# SignalGen_DualChannel.net
KiCad netlist of a schematic drawn in Altium Designer
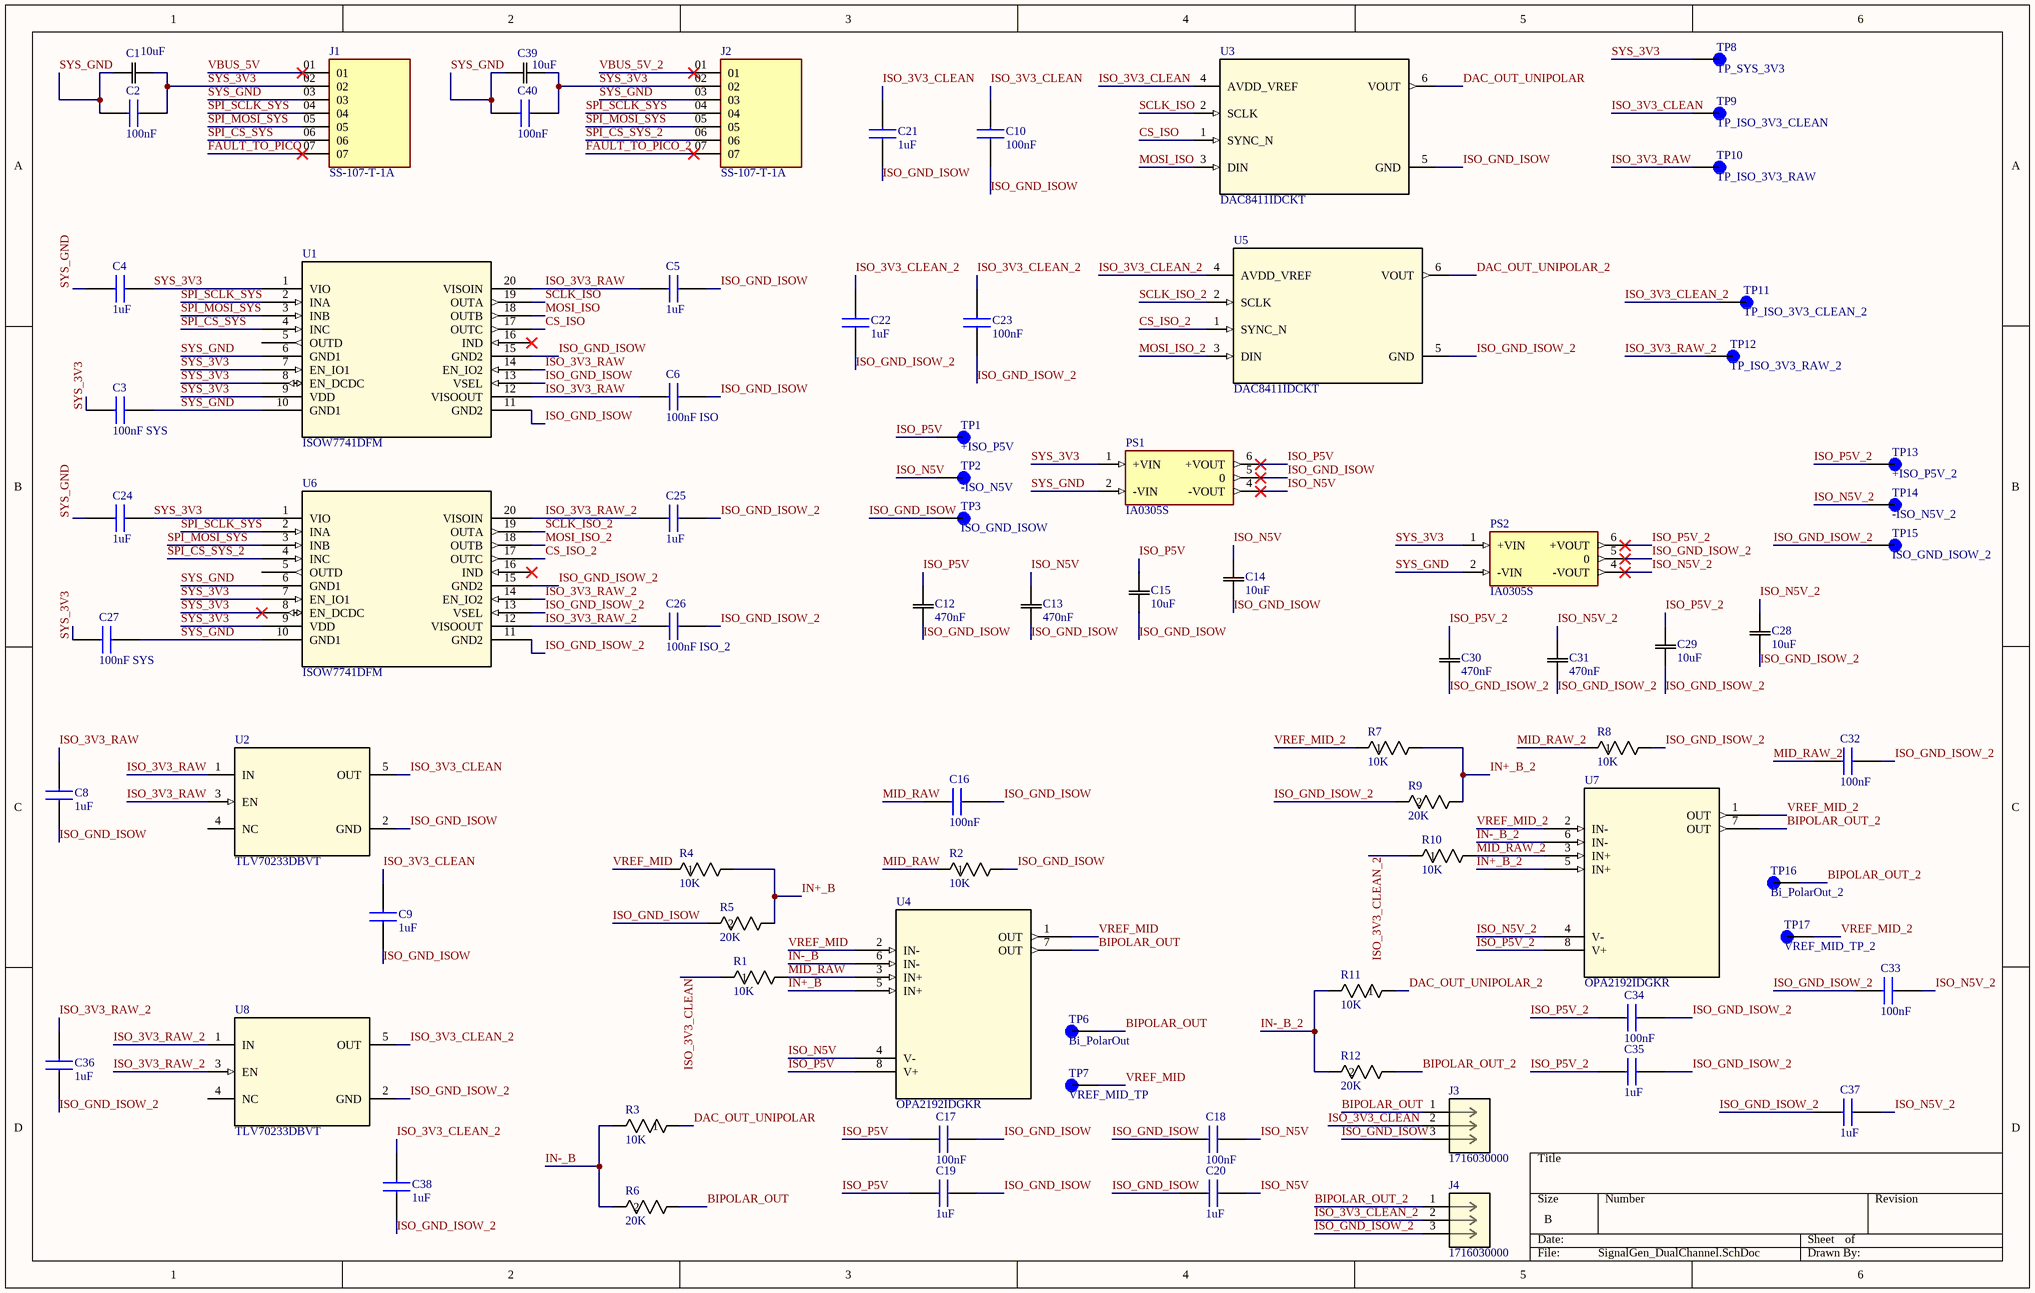
[diagram p0: SignalGen_DualChannel.SchDoc]

(export (version "E")
  (design (tool "Eeschema 10.0.6"))
  (components
    (comp (ref "C1")
      (value "10uF")
      (footprint "G-21_MUR")
      (description "Description")
      (fields
        (field (name "MANUFACTURER_PART_NUMBER") "GRM21BR61E106KA73L")
        (field (name "COPYRIGHT") "Copyright (C) 2025 Ultra Librarian. All rights reserved.")
      )
      (libsource (lib "GRM21BR61E106KA73L") (part "GRM21BR61E106KA73L"))
    )
    (comp (ref "C2")
      (value "100nF")
      (footprint "CAPC1608X90N")
      (description "Cap Ceramic 0.1uF 25V X7R 10% Pad SMD 0603 125C T/R")
      (fields
        (field (name "MOUSER PART NUMBER") "603-CC603KRX7R8BB104")
        (field (name "MANUFACTURER_PART_NUMBER") "CC0603KRX7R8BB104")
      )
      (libsource (lib "CC0603KRX7R8BB104") (part "CC0603KRX7R8BB104"))
    )
    (comp (ref "C3")
      (value "100nF SYS")
      (footprint "CAPC1608X90N")
      (description "Cap Ceramic 0.1uF 25V X7R 10% Pad SMD 0603 125C T/R")
      (fields
        (field (name "MOUSER PART NUMBER") "603-CC603KRX7R8BB104")
        (field (name "MANUFACTURER_PART_NUMBER") "CC0603KRX7R8BB104")
      )
      (libsource (lib "CC0603KRX7R8BB104") (part "CC0603KRX7R8BB104"))
    )
    (comp (ref "C4")
      (value "1uF")
      (footprint "INDC1608X90N")
      (description "Taiyo Yuden CAP, MLCC, 0603, 16V, X7R, 1 uF 10 %, T&R")
      (fields (field (name "MANUFACTURER_PART_NUMBER") "MBASE168SB7105KTNA18"))
      (libsource (lib "MBASE168SB7105KTNA18") (part "MBASE168SB7105KTNA18"))
    )
    (comp (ref "C5")
      (value "1uF")
      (footprint "INDC1608X90N")
      (description "Taiyo Yuden CAP, MLCC, 0603, 16V, X7R, 1 uF 10 %, T&R")
      (fields (field (name "MANUFACTURER_PART_NUMBER") "MBASE168SB7105KTNA18"))
      (libsource (lib "MBASE168SB7105KTNA18") (part "MBASE168SB7105KTNA18"))
    )
    (comp (ref "C6")
      (value "100nF ISO")
      (footprint "CAPC1608X90N")
      (description "Cap Ceramic 0.1uF 25V X7R 10% Pad SMD 0603 125C T/R")
      (fields
        (field (name "MOUSER PART NUMBER") "603-CC603KRX7R8BB104")
        (field (name "MANUFACTURER_PART_NUMBER") "CC0603KRX7R8BB104")
      )
      (libsource (lib "CC0603KRX7R8BB104") (part "CC0603KRX7R8BB104"))
    )
    (comp (ref "C8")
      (value "1uF")
      (footprint "INDC1608X90N")
      (description "Taiyo Yuden CAP, MLCC, 0603, 16V, X7R, 1 uF 10 %, T&R")
      (fields (field (name "MANUFACTURER_PART_NUMBER") "MBASE168SB7105KTNA18"))
      (libsource (lib "MBASE168SB7105KTNA18") (part "MBASE168SB7105KTNA18"))
    )
    (comp (ref "C9")
      (value "1uF")
      (footprint "INDC1608X90N")
      (description "Taiyo Yuden CAP, MLCC, 0603, 16V, X7R, 1 uF 10 %, T&R")
      (fields (field (name "MANUFACTURER_PART_NUMBER") "MBASE168SB7105KTNA18"))
      (libsource (lib "MBASE168SB7105KTNA18") (part "MBASE168SB7105KTNA18"))
    )
    (comp (ref "C10")
      (value "100nF")
      (footprint "CAPC1608X90N")
      (description "Cap Ceramic 0.1uF 25V X7R 10% Pad SMD 0603 125C T/R")
      (fields
        (field (name "MOUSER PART NUMBER") "603-CC603KRX7R8BB104")
        (field (name "MANUFACTURER_PART_NUMBER") "CC0603KRX7R8BB104")
      )
      (libsource (lib "CC0603KRX7R8BB104") (part "CC0603KRX7R8BB104"))
    )
    (comp (ref "C12")
      (value "470nF")
      (footprint "CAP_1608_TDK")
      (description "CAPACITOR; SMT (0603); CERAMIC CHIP; 0.47UF; 50V; TOL=10%; TG=-55 DEGC TO +125 DEGC; TC=X7R; AUTO")
      (fields
        (field (name "MANUFACTURER_PART_NUMBER") "C1608X7R1H474K080AC")
        (field (name "COPYRIGHT") "Copyright (C) 2026 Ultra Librarian. All rights reserved.")
      )
      (libsource (lib "C1608X7R1H474K080AC") (part "C1608X7R1H474K080AC"))
    )
    (comp (ref "C13")
      (value "470nF")
      (footprint "CAP_1608_TDK")
      (description "CAPACITOR; SMT (0603); CERAMIC CHIP; 0.47UF; 50V; TOL=10%; TG=-55 DEGC TO +125 DEGC; TC=X7R; AUTO")
      (fields
        (field (name "MANUFACTURER_PART_NUMBER") "C1608X7R1H474K080AC")
        (field (name "COPYRIGHT") "Copyright (C) 2026 Ultra Librarian. All rights reserved.")
      )
      (libsource (lib "C1608X7R1H474K080AC") (part "C1608X7R1H474K080AC"))
    )
    (comp (ref "C14")
      (value "10uF")
      (footprint "G-21_MUR")
      (description "Description")
      (fields
        (field (name "MANUFACTURER_PART_NUMBER") "GRM21BR61E106KA73L")
        (field (name "COPYRIGHT") "Copyright (C) 2025 Ultra Librarian. All rights reserved.")
      )
      (libsource (lib "GRM21BR61E106KA73L") (part "GRM21BR61E106KA73L"))
    )
    (comp (ref "C15")
      (value "10uF")
      (footprint "G-21_MUR")
      (description "Description")
      (fields
        (field (name "MANUFACTURER_PART_NUMBER") "GRM21BR61E106KA73L")
        (field (name "COPYRIGHT") "Copyright (C) 2025 Ultra Librarian. All rights reserved.")
      )
      (libsource (lib "GRM21BR61E106KA73L") (part "GRM21BR61E106KA73L"))
    )
    (comp (ref "C16")
      (value "100nF")
      (footprint "CAPC1608X90N")
      (description "Cap Ceramic 0.1uF 25V X7R 10% Pad SMD 0603 125C T/R")
      (fields
        (field (name "MOUSER PART NUMBER") "603-CC603KRX7R8BB104")
        (field (name "MANUFACTURER_PART_NUMBER") "CC0603KRX7R8BB104")
      )
      (libsource (lib "CC0603KRX7R8BB104") (part "CC0603KRX7R8BB104"))
    )
    (comp (ref "C17")
      (value "100nF")
      (footprint "CAPC1608X90N")
      (description "Cap Ceramic 0.1uF 25V X7R 10% Pad SMD 0603 125C T/R")
      (fields
        (field (name "MOUSER PART NUMBER") "603-CC603KRX7R8BB104")
        (field (name "MANUFACTURER_PART_NUMBER") "CC0603KRX7R8BB104")
      )
      (libsource (lib "CC0603KRX7R8BB104") (part "CC0603KRX7R8BB104"))
    )
    (comp (ref "C18")
      (value "100nF")
      (footprint "CAPC1608X90N")
      (description "Cap Ceramic 0.1uF 25V X7R 10% Pad SMD 0603 125C T/R")
      (fields
        (field (name "MOUSER PART NUMBER") "603-CC603KRX7R8BB104")
        (field (name "MANUFACTURER_PART_NUMBER") "CC0603KRX7R8BB104")
      )
      (libsource (lib "CC0603KRX7R8BB104") (part "CC0603KRX7R8BB104"))
    )
    (comp (ref "C19")
      (value "1uF")
      (footprint "INDC1608X90N")
      (description "Taiyo Yuden CAP, MLCC, 0603, 16V, X7R, 1 uF 10 %, T&R")
      (fields (field (name "MANUFACTURER_PART_NUMBER") "MBASE168SB7105KTNA18"))
      (libsource (lib "MBASE168SB7105KTNA18") (part "MBASE168SB7105KTNA18"))
    )
    (comp (ref "C20")
      (value "1uF")
      (footprint "INDC1608X90N")
      (description "Taiyo Yuden CAP, MLCC, 0603, 16V, X7R, 1 uF 10 %, T&R")
      (fields (field (name "MANUFACTURER_PART_NUMBER") "MBASE168SB7105KTNA18"))
      (libsource (lib "MBASE168SB7105KTNA18") (part "MBASE168SB7105KTNA18"))
    )
    (comp (ref "C21")
      (value "1uF")
      (footprint "INDC1608X90N")
      (description "Taiyo Yuden CAP, MLCC, 0603, 16V, X7R, 1 uF 10 %, T&R")
      (fields (field (name "MANUFACTURER_PART_NUMBER") "MBASE168SB7105KTNA18"))
      (libsource (lib "MBASE168SB7105KTNA18") (part "MBASE168SB7105KTNA18"))
    )
    (comp (ref "C22")
      (value "1uF")
      (footprint "INDC1608X90N")
      (description "Taiyo Yuden CAP, MLCC, 0603, 16V, X7R, 1 uF 10 %, T&R")
      (fields (field (name "MANUFACTURER_PART_NUMBER") "MBASE168SB7105KTNA18"))
      (libsource (lib "MBASE168SB7105KTNA18") (part "MBASE168SB7105KTNA18"))
    )
    (comp (ref "C23")
      (value "100nF")
      (footprint "CAPC1608X90N")
      (description "Cap Ceramic 0.1uF 25V X7R 10% Pad SMD 0603 125C T/R")
      (fields
        (field (name "MOUSER PART NUMBER") "603-CC603KRX7R8BB104")
        (field (name "MANUFACTURER_PART_NUMBER") "CC0603KRX7R8BB104")
      )
      (libsource (lib "CC0603KRX7R8BB104") (part "CC0603KRX7R8BB104"))
    )
    (comp (ref "C24")
      (value "1uF")
      (footprint "INDC1608X90N")
      (description "Taiyo Yuden CAP, MLCC, 0603, 16V, X7R, 1 uF 10 %, T&R")
      (fields (field (name "MANUFACTURER_PART_NUMBER") "MBASE168SB7105KTNA18"))
      (libsource (lib "MBASE168SB7105KTNA18") (part "MBASE168SB7105KTNA18"))
    )
    (comp (ref "C25")
      (value "1uF")
      (footprint "INDC1608X90N")
      (description "Taiyo Yuden CAP, MLCC, 0603, 16V, X7R, 1 uF 10 %, T&R")
      (fields (field (name "MANUFACTURER_PART_NUMBER") "MBASE168SB7105KTNA18"))
      (libsource (lib "MBASE168SB7105KTNA18") (part "MBASE168SB7105KTNA18"))
    )
    (comp (ref "C26")
      (value "100nF ISO_2")
      (footprint "CAPC1608X90N")
      (description "Cap Ceramic 0.1uF 25V X7R 10% Pad SMD 0603 125C T/R")
      (fields
        (field (name "MOUSER PART NUMBER") "603-CC603KRX7R8BB104")
        (field (name "MANUFACTURER_PART_NUMBER") "CC0603KRX7R8BB104")
      )
      (libsource (lib "CC0603KRX7R8BB104") (part "CC0603KRX7R8BB104"))
    )
    (comp (ref "C27")
      (value "100nF SYS")
      (footprint "CAPC1608X90N")
      (description "Cap Ceramic 0.1uF 25V X7R 10% Pad SMD 0603 125C T/R")
      (fields
        (field (name "MOUSER PART NUMBER") "603-CC603KRX7R8BB104")
        (field (name "MANUFACTURER_PART_NUMBER") "CC0603KRX7R8BB104")
      )
      (libsource (lib "CC0603KRX7R8BB104") (part "CC0603KRX7R8BB104"))
    )
    (comp (ref "C28")
      (value "10uF")
      (footprint "G-21_MUR")
      (description "Description")
      (fields
        (field (name "MANUFACTURER_PART_NUMBER") "GRM21BR61E106KA73L")
        (field (name "COPYRIGHT") "Copyright (C) 2025 Ultra Librarian. All rights reserved.")
      )
      (libsource (lib "GRM21BR61E106KA73L") (part "GRM21BR61E106KA73L"))
    )
    (comp (ref "C29")
      (value "10uF")
      (footprint "G-21_MUR")
      (description "Description")
      (fields
        (field (name "MANUFACTURER_PART_NUMBER") "GRM21BR61E106KA73L")
        (field (name "COPYRIGHT") "Copyright (C) 2025 Ultra Librarian. All rights reserved.")
      )
      (libsource (lib "GRM21BR61E106KA73L") (part "GRM21BR61E106KA73L"))
    )
    (comp (ref "C30")
      (value "470nF")
      (footprint "CAP_1608_TDK")
      (description "CAPACITOR; SMT (0603); CERAMIC CHIP; 0.47UF; 50V; TOL=10%; TG=-55 DEGC TO +125 DEGC; TC=X7R; AUTO")
      (fields
        (field (name "MANUFACTURER_PART_NUMBER") "C1608X7R1H474K080AC")
        (field (name "COPYRIGHT") "Copyright (C) 2026 Ultra Librarian. All rights reserved.")
      )
      (libsource (lib "C1608X7R1H474K080AC") (part "C1608X7R1H474K080AC"))
    )
    (comp (ref "C31")
      (value "470nF")
      (footprint "CAP_1608_TDK")
      (description "CAPACITOR; SMT (0603); CERAMIC CHIP; 0.47UF; 50V; TOL=10%; TG=-55 DEGC TO +125 DEGC; TC=X7R; AUTO")
      (fields
        (field (name "MANUFACTURER_PART_NUMBER") "C1608X7R1H474K080AC")
        (field (name "COPYRIGHT") "Copyright (C) 2026 Ultra Librarian. All rights reserved.")
      )
      (libsource (lib "C1608X7R1H474K080AC") (part "C1608X7R1H474K080AC"))
    )
    (comp (ref "C32")
      (value "100nF")
      (footprint "CAPC1608X90N")
      (description "Cap Ceramic 0.1uF 25V X7R 10% Pad SMD 0603 125C T/R")
      (fields
        (field (name "MOUSER PART NUMBER") "603-CC603KRX7R8BB104")
        (field (name "MANUFACTURER_PART_NUMBER") "CC0603KRX7R8BB104")
      )
      (libsource (lib "CC0603KRX7R8BB104") (part "CC0603KRX7R8BB104"))
    )
    (comp (ref "C33")
      (value "100nF")
      (footprint "CAPC1608X90N")
      (description "Cap Ceramic 0.1uF 25V X7R 10% Pad SMD 0603 125C T/R")
      (fields
        (field (name "MOUSER PART NUMBER") "603-CC603KRX7R8BB104")
        (field (name "MANUFACTURER_PART_NUMBER") "CC0603KRX7R8BB104")
      )
      (libsource (lib "CC0603KRX7R8BB104") (part "CC0603KRX7R8BB104"))
    )
    (comp (ref "C34")
      (value "100nF")
      (footprint "CAPC1608X90N")
      (description "Cap Ceramic 0.1uF 25V X7R 10% Pad SMD 0603 125C T/R")
      (fields
        (field (name "MOUSER PART NUMBER") "603-CC603KRX7R8BB104")
        (field (name "MANUFACTURER_PART_NUMBER") "CC0603KRX7R8BB104")
      )
      (libsource (lib "CC0603KRX7R8BB104") (part "CC0603KRX7R8BB104"))
    )
    (comp (ref "C35")
      (value "1uF")
      (footprint "INDC1608X90N")
      (description "Taiyo Yuden CAP, MLCC, 0603, 16V, X7R, 1 uF 10 %, T&R")
      (fields (field (name "MANUFACTURER_PART_NUMBER") "MBASE168SB7105KTNA18"))
      (libsource (lib "MBASE168SB7105KTNA18") (part "MBASE168SB7105KTNA18"))
    )
    (comp (ref "C36")
      (value "1uF")
      (footprint "INDC1608X90N")
      (description "Taiyo Yuden CAP, MLCC, 0603, 16V, X7R, 1 uF 10 %, T&R")
      (fields (field (name "MANUFACTURER_PART_NUMBER") "MBASE168SB7105KTNA18"))
      (libsource (lib "MBASE168SB7105KTNA18") (part "MBASE168SB7105KTNA18"))
    )
    (comp (ref "C37")
      (value "1uF")
      (footprint "INDC1608X90N")
      (description "Taiyo Yuden CAP, MLCC, 0603, 16V, X7R, 1 uF 10 %, T&R")
      (fields (field (name "MANUFACTURER_PART_NUMBER") "MBASE168SB7105KTNA18"))
      (libsource (lib "MBASE168SB7105KTNA18") (part "MBASE168SB7105KTNA18"))
    )
    (comp (ref "C38")
      (value "1uF")
      (footprint "INDC1608X90N")
      (description "Taiyo Yuden CAP, MLCC, 0603, 16V, X7R, 1 uF 10 %, T&R")
      (fields (field (name "MANUFACTURER_PART_NUMBER") "MBASE168SB7105KTNA18"))
      (libsource (lib "MBASE168SB7105KTNA18") (part "MBASE168SB7105KTNA18"))
    )
    (comp (ref "C39")
      (value "10uF")
      (footprint "G-21_MUR")
      (description "Description")
      (fields
        (field (name "MANUFACTURER_PART_NUMBER") "GRM21BR61E106KA73L")
        (field (name "COPYRIGHT") "Copyright (C) 2025 Ultra Librarian. All rights reserved.")
      )
      (libsource (lib "GRM21BR61E106KA73L") (part "GRM21BR61E106KA73L"))
    )
    (comp (ref "C40")
      (value "100nF")
      (footprint "CAPC1608X90N")
      (description "Cap Ceramic 0.1uF 25V X7R 10% Pad SMD 0603 125C T/R")
      (fields
        (field (name "MOUSER PART NUMBER") "603-CC603KRX7R8BB104")
        (field (name "MANUFACTURER_PART_NUMBER") "CC0603KRX7R8BB104")
      )
      (libsource (lib "CC0603KRX7R8BB104") (part "CC0603KRX7R8BB104"))
    )
    (comp (ref "J1")
      (value "SS-107-T-1A")
      (footprint "SAMTEC_SS-107-T-1A")
      (libsource (lib "SS-107-T-1A") (part "SS-107-T-1A"))
    )
    (comp (ref "J2")
      (value "SS-107-T-1A")
      (footprint "SAMTEC_SS-107-T-1A")
      (libsource (lib "SS-107-T-1A") (part "SS-107-T-1A"))
    )
    (comp (ref "J3")
      (value "1716030000")
      (footprint "CONN_LM 5.080390_WED")
      (description "Description")
      (fields (field (name "COPYRIGHT") "Copyright (C) 2025 Ultra Librarian. All rights reserved."))
      (libsource (lib "1716030000") (part "1716030000"))
    )
    (comp (ref "J4")
      (value "1716030000")
      (footprint "CONN_LM 5.080390_WED")
      (description "Description")
      (fields (field (name "COPYRIGHT") "Copyright (C) 2025 Ultra Librarian. All rights reserved."))
      (libsource (lib "1716030000") (part "1716030000"))
    )
    (comp (ref "PS1")
      (value "IA0305S")
      (footprint "XP_IA0305S")
      (description "DC DC CONVERTER +/-5V 1W")
      (libsource (lib "IA0305S") (part "IA0305S"))
    )
    (comp (ref "PS2")
      (value "IA0305S")
      (footprint "XP_IA0305S")
      (description "DC DC CONVERTER +/-5V 1W")
      (libsource (lib "IA0305S") (part "IA0305S"))
    )
    (comp (ref "R1")
      (value "10K")
      (footprint "RC0603N_YAG")
      (description "RES SMD 10kO 1% 1/10W 0603")
      (fields
        (field (name "MANUFACTURER_PART_NUMBER") "RC0603FR-0710KL")
        (field (name "COPYRIGHT") "Copyright (C) 2025 Ultra Librarian. All rights reserved.")
      )
      (libsource (lib "RC0603FR-0710KL") (part "RC0603FR-0710KL"))
    )
    (comp (ref "R2")
      (value "10K")
      (footprint "RC0603N_YAG")
      (description "RES SMD 10kO 1% 1/10W 0603")
      (fields
        (field (name "MANUFACTURER_PART_NUMBER") "RC0603FR-0710KL")
        (field (name "COPYRIGHT") "Copyright (C) 2025 Ultra Librarian. All rights reserved.")
      )
      (libsource (lib "RC0603FR-0710KL") (part "RC0603FR-0710KL"))
    )
    (comp (ref "R3")
      (value "10K")
      (footprint "RC0603N_YAG")
      (description "RES SMD 10kO 1% 1/10W 0603")
      (fields
        (field (name "MANUFACTURER_PART_NUMBER") "RC0603FR-0710KL")
        (field (name "COPYRIGHT") "Copyright (C) 2025 Ultra Librarian. All rights reserved.")
      )
      (libsource (lib "RC0603FR-0710KL") (part "RC0603FR-0710KL"))
    )
    (comp (ref "R4")
      (value "10K")
      (footprint "RC0603N_YAG")
      (description "RES SMD 10kO 1% 1/10W 0603")
      (fields
        (field (name "MANUFACTURER_PART_NUMBER") "RC0603FR-0710KL")
        (field (name "COPYRIGHT") "Copyright (C) 2025 Ultra Librarian. All rights reserved.")
      )
      (libsource (lib "RC0603FR-0710KL") (part "RC0603FR-0710KL"))
    )
    (comp (ref "R5")
      (value "20K")
      (footprint "RC0603N_YAG")
      (description "Description")
      (fields
        (field (name "MANUFACTURER_PART_NUMBER") "RC0603FR-0720KL")
        (field (name "COPYRIGHT") "Copyright (C) 2025 Ultra Librarian. All rights reserved.")
      )
      (libsource (lib "RC0603FR-0720KL") (part "RC0603FR-0720KL"))
    )
    (comp (ref "R6")
      (value "20K")
      (footprint "RC0603N_YAG")
      (description "Description")
      (fields
        (field (name "MANUFACTURER_PART_NUMBER") "RC0603FR-0720KL")
        (field (name "COPYRIGHT") "Copyright (C) 2025 Ultra Librarian. All rights reserved.")
      )
      (libsource (lib "RC0603FR-0720KL") (part "RC0603FR-0720KL"))
    )
    (comp (ref "R7")
      (value "10K")
      (footprint "RC0603N_YAG")
      (description "RES SMD 10kO 1% 1/10W 0603")
      (fields
        (field (name "MANUFACTURER_PART_NUMBER") "RC0603FR-0710KL")
        (field (name "COPYRIGHT") "Copyright (C) 2025 Ultra Librarian. All rights reserved.")
      )
      (libsource (lib "RC0603FR-0710KL") (part "RC0603FR-0710KL"))
    )
    (comp (ref "R8")
      (value "10K")
      (footprint "RC0603N_YAG")
      (description "RES SMD 10kO 1% 1/10W 0603")
      (fields
        (field (name "MANUFACTURER_PART_NUMBER") "RC0603FR-0710KL")
        (field (name "COPYRIGHT") "Copyright (C) 2025 Ultra Librarian. All rights reserved.")
      )
      (libsource (lib "RC0603FR-0710KL") (part "RC0603FR-0710KL"))
    )
    (comp (ref "R9")
      (value "20K")
      (footprint "RC0603N_YAG")
      (description "Description")
      (fields
        (field (name "MANUFACTURER_PART_NUMBER") "RC0603FR-0720KL")
        (field (name "COPYRIGHT") "Copyright (C) 2025 Ultra Librarian. All rights reserved.")
      )
      (libsource (lib "RC0603FR-0720KL") (part "RC0603FR-0720KL"))
    )
    (comp (ref "R10")
      (value "10K")
      (footprint "RC0603N_YAG")
      (description "RES SMD 10kO 1% 1/10W 0603")
      (fields
        (field (name "MANUFACTURER_PART_NUMBER") "RC0603FR-0710KL")
        (field (name "COPYRIGHT") "Copyright (C) 2025 Ultra Librarian. All rights reserved.")
      )
      (libsource (lib "RC0603FR-0710KL") (part "RC0603FR-0710KL"))
    )
    (comp (ref "R11")
      (value "10K")
      (footprint "RC0603N_YAG")
      (description "RES SMD 10kO 1% 1/10W 0603")
      (fields
        (field (name "MANUFACTURER_PART_NUMBER") "RC0603FR-0710KL")
        (field (name "COPYRIGHT") "Copyright (C) 2025 Ultra Librarian. All rights reserved.")
      )
      (libsource (lib "RC0603FR-0710KL") (part "RC0603FR-0710KL"))
    )
    (comp (ref "R12")
      (value "20K")
      (footprint "RC0603N_YAG")
      (description "Description")
      (fields
        (field (name "MANUFACTURER_PART_NUMBER") "RC0603FR-0720KL")
        (field (name "COPYRIGHT") "Copyright (C) 2025 Ultra Librarian. All rights reserved.")
      )
      (libsource (lib "RC0603FR-0720KL") (part "RC0603FR-0720KL"))
    )
    (comp (ref "TP1")
      (value "+ISO_P5V")
      (footprint "KEYSTONE_5016")
      (description "Test Point Compact SMT Phos Bronze/Silver 1000pc Tape & Reel ¦ Keystone Electronics 5016")
      (fields (field (name "MF") "Keystone Electronics") (field (name "MP") "5016"))
      (libsource (lib "5016") (part "5016"))
    )
    (comp (ref "TP2")
      (value "-ISO_N5V")
      (footprint "KEYSTONE_5016")
      (description "Test Point Compact SMT Phos Bronze/Silver 1000pc Tape & Reel ¦ Keystone Electronics 5016")
      (fields (field (name "MF") "Keystone Electronics") (field (name "MP") "5016"))
      (libsource (lib "5016") (part "5016"))
    )
    (comp (ref "TP3")
      (value "ISO_GND_ISOW")
      (footprint "KEYSTONE_5016")
      (description "Test Point Compact SMT Phos Bronze/Silver 1000pc Tape & Reel ¦ Keystone Electronics 5016")
      (fields (field (name "MF") "Keystone Electronics") (field (name "MP") "5016"))
      (libsource (lib "5016") (part "5016"))
    )
    (comp (ref "TP6")
      (value "Bi_PolarOut")
      (footprint "KEYSTONE_5016")
      (description "Test Point Compact SMT Phos Bronze/Silver 1000pc Tape & Reel ¦ Keystone Electronics 5016")
      (fields (field (name "MF") "Keystone Electronics") (field (name "MP") "5016"))
      (libsource (lib "5016") (part "5016"))
    )
    (comp (ref "TP7")
      (value "VREF_MID_TP")
      (footprint "KEYSTONE_5016")
      (description "Test Point Compact SMT Phos Bronze/Silver 1000pc Tape & Reel ¦ Keystone Electronics 5016")
      (fields (field (name "MF") "Keystone Electronics") (field (name "MP") "5016"))
      (libsource (lib "5016") (part "5016"))
    )
    (comp (ref "TP8")
      (value "TP_SYS_3V3")
      (footprint "KEYSTONE_5016")
      (description "Test Point Compact SMT Phos Bronze/Silver 1000pc Tape & Reel ¦ Keystone Electronics 5016")
      (fields (field (name "MF") "Keystone Electronics") (field (name "MP") "5016"))
      (libsource (lib "5016") (part "5016"))
    )
    (comp (ref "TP9")
      (value "TP_ISO_3V3_CLEAN")
      (footprint "KEYSTONE_5016")
      (description "Test Point Compact SMT Phos Bronze/Silver 1000pc Tape & Reel ¦ Keystone Electronics 5016")
      (fields (field (name "MF") "Keystone Electronics") (field (name "MP") "5016"))
      (libsource (lib "5016") (part "5016"))
    )
    (comp (ref "TP10")
      (value "TP_ISO_3V3_RAW")
      (footprint "KEYSTONE_5016")
      (description "Test Point Compact SMT Phos Bronze/Silver 1000pc Tape & Reel ¦ Keystone Electronics 5016")
      (fields (field (name "MF") "Keystone Electronics") (field (name "MP") "5016"))
      (libsource (lib "5016") (part "5016"))
    )
    (comp (ref "TP11")
      (value "TP_ISO_3V3_CLEAN_2")
      (footprint "KEYSTONE_5016")
      (description "Test Point Compact SMT Phos Bronze/Silver 1000pc Tape & Reel ¦ Keystone Electronics 5016")
      (fields (field (name "MF") "Keystone Electronics") (field (name "MP") "5016"))
      (libsource (lib "5016") (part "5016"))
    )
    (comp (ref "TP12")
      (value "TP_ISO_3V3_RAW_2")
      (footprint "KEYSTONE_5016")
      (description "Test Point Compact SMT Phos Bronze/Silver 1000pc Tape & Reel ¦ Keystone Electronics 5016")
      (fields (field (name "MF") "Keystone Electronics") (field (name "MP") "5016"))
      (libsource (lib "5016") (part "5016"))
    )
    (comp (ref "TP13")
      (value "+ISO_P5V_2")
      (footprint "KEYSTONE_5016")
      (description "Test Point Compact SMT Phos Bronze/Silver 1000pc Tape & Reel ¦ Keystone Electronics 5016")
      (fields (field (name "MF") "Keystone Electronics") (field (name "MP") "5016"))
      (libsource (lib "5016") (part "5016"))
    )
    (comp (ref "TP14")
      (value "-ISO_N5V_2")
      (footprint "KEYSTONE_5016")
      (description "Test Point Compact SMT Phos Bronze/Silver 1000pc Tape & Reel ¦ Keystone Electronics 5016")
      (fields (field (name "MF") "Keystone Electronics") (field (name "MP") "5016"))
      (libsource (lib "5016") (part "5016"))
    )
    (comp (ref "TP15")
      (value "ISO_GND_ISOW_2")
      (footprint "KEYSTONE_5016")
      (description "Test Point Compact SMT Phos Bronze/Silver 1000pc Tape & Reel ¦ Keystone Electronics 5016")
      (fields (field (name "MF") "Keystone Electronics") (field (name "MP") "5016"))
      (libsource (lib "5016") (part "5016"))
    )
    (comp (ref "TP16")
      (value "Bi_PolarOut_2")
      (footprint "KEYSTONE_5016")
      (description "Test Point Compact SMT Phos Bronze/Silver 1000pc Tape & Reel ¦ Keystone Electronics 5016")
      (fields (field (name "MF") "Keystone Electronics") (field (name "MP") "5016"))
      (libsource (lib "5016") (part "5016"))
    )
    (comp (ref "TP17")
      (value "VREF_MID_TP_2")
      (footprint "KEYSTONE_5016")
      (description "Test Point Compact SMT Phos Bronze/Silver 1000pc Tape & Reel ¦ Keystone Electronics 5016")
      (fields (field (name "MF") "Keystone Electronics") (field (name "MP") "5016"))
      (libsource (lib "5016") (part "5016"))
    )
    (comp (ref "U1")
      (value "ISOW7741DFM")
      (footprint "SOIC20_DFM_TEX")
      (fields (field (name "COPYRIGHT") "Copyright (C) 2026 Ultra Librarian. All rights reserved."))
      (libsource (lib "ISOW7741DFM") (part "ISOW7741DFM"))
    )
    (comp (ref "U2")
      (value "TLV70233DBVT")
      (footprint "DBV0005A_N")
      (description "300-mA, high-PSRR, low-IQ, low-dropout voltage regulator with enable 5-SOT-23 -40 to 125")
      (fields
        (field (name "PARTNUMBER") "TLV70212DBVR")
        (field (name "ALTERNATE_PARTNUMBER") "TLV70212DBVT")
        (field (name "COPYRIGHT") "Copyright (C) 2026 Ultra Librarian. All rights reserved.")
      )
      (libsource (lib "TLV70233DBVT") (part "TLV70233DBVT"))
    )
    (comp (ref "U3")
      (value "DAC8411IDCKT")
      (footprint "DCK0006A_N")
      (description "16bit, Single Channel, 80uA, 2.0V-5.5V DAC in SC70 Package 6-SC70 -40 to 125")
      (fields
        (field (name "PARTNUMBER") "DAC8411IDCKR")
        (field (name "MANUFACTURER") "Texas Instruments")
        (field (name "COPYRIGHT") "Copyright (C) 2025 Ultra Librarian. All rights reserved.")
      )
      (libsource (lib "DAC8411IDCKT") (part "DAC8411IDCKT"))
    )
    (comp (ref "U4")
      (value "OPA2192IDGKR")
      (footprint "DGK0008A_N_TEX")
      (fields (field (name "COPYRIGHT") "Copyright (C) 2025 Ultra Librarian. All rights reserved."))
      (libsource (lib "OPA2192IDGKR") (part "OPA2192IDGKR"))
    )
    (comp (ref "U5")
      (value "DAC8411IDCKT")
      (footprint "DCK0006A_N")
      (description "16bit, Single Channel, 80uA, 2.0V-5.5V DAC in SC70 Package 6-SC70 -40 to 125")
      (fields
        (field (name "PARTNUMBER") "DAC8411IDCKR")
        (field (name "MANUFACTURER") "Texas Instruments")
        (field (name "COPYRIGHT") "Copyright (C) 2025 Ultra Librarian. All rights reserved.")
      )
      (libsource (lib "DAC8411IDCKT") (part "DAC8411IDCKT"))
    )
    (comp (ref "U6")
      (value "ISOW7741DFM")
      (footprint "SOIC20_DFM_TEX")
      (fields (field (name "COPYRIGHT") "Copyright (C) 2026 Ultra Librarian. All rights reserved."))
      (libsource (lib "ISOW7741DFM") (part "ISOW7741DFM"))
    )
    (comp (ref "U7")
      (value "OPA2192IDGKR")
      (footprint "DGK0008A_N_TEX")
      (fields (field (name "COPYRIGHT") "Copyright (C) 2025 Ultra Librarian. All rights reserved."))
      (libsource (lib "OPA2192IDGKR") (part "OPA2192IDGKR"))
    )
    (comp (ref "U8")
      (value "TLV70233DBVT")
      (footprint "DBV0005A_N")
      (description "300-mA, high-PSRR, low-IQ, low-dropout voltage regulator with enable 5-SOT-23 -40 to 125")
      (fields
        (field (name "PARTNUMBER") "TLV70212DBVR")
        (field (name "ALTERNATE_PARTNUMBER") "TLV70212DBVT")
        (field (name "COPYRIGHT") "Copyright (C) 2026 Ultra Librarian. All rights reserved.")
      )
      (libsource (lib "TLV70233DBVT") (part "TLV70233DBVT"))
    )
  )
  (nets
    (net (code "1") (name "/BIPOLAR_OUT") (class "Default")
      (node (ref "J3") (pin "1") (pinfunction "1_1") (pintype "passive"))
      (node (ref "R6") (pin "1") (pinfunction "1_1") (pintype "passive"))
      (node (ref "TP6") (pin "TP") (pinfunction "TP_TP") (pintype "passive"))
      (node (ref "U4") (pin "7") (pinfunction "OUT_7") (pintype "output"))
    )
    (net (code "2") (name "/BIPOLAR_OUT_2") (class "Default")
      (node (ref "J4") (pin "1") (pinfunction "1_1") (pintype "passive"))
      (node (ref "R12") (pin "1") (pinfunction "1_1") (pintype "passive"))
      (node (ref "TP16") (pin "TP") (pinfunction "TP_TP") (pintype "passive"))
      (node (ref "U7") (pin "7") (pinfunction "OUT_7") (pintype "output"))
    )
    (net (code "3") (name "/CS_ISO") (class "Default")
      (node (ref "U1") (pin "17") (pinfunction "OUTC_17") (pintype "output"))
      (node (ref "U3") (pin "1") (pinfunction "SYNC_N_1") (pintype "input"))
    )
    (net (code "4") (name "/CS_ISO_2") (class "Default")
      (node (ref "U5") (pin "1") (pinfunction "SYNC_N_1") (pintype "input"))
      (node (ref "U6") (pin "17") (pinfunction "OUTC_17") (pintype "output"))
    )
    (net (code "5") (name "/DAC_OUT_UNIPOLAR") (class "Default")
      (node (ref "R3") (pin "1") (pinfunction "1_1") (pintype "passive"))
      (node (ref "U3") (pin "6") (pinfunction "VOUT_6") (pintype "output"))
    )
    (net (code "6") (name "/DAC_OUT_UNIPOLAR_2") (class "Default")
      (node (ref "R11") (pin "1") (pinfunction "1_1") (pintype "passive"))
      (node (ref "U5") (pin "6") (pinfunction "VOUT_6") (pintype "output"))
    )
    (net (code "7") (name "/FAULT_TO_PICO") (class "Default")
      (node (ref "J1") (pin "07") (pinfunction "07_07") (pintype "passive+no_connect"))
    )
    (net (code "8") (name "/FAULT_TO_PICO_2") (class "Default")
      (node (ref "J2") (pin "07") (pinfunction "07_07") (pintype "passive+no_connect"))
    )
    (net (code "9") (name "/IN+_B") (class "Default")
      (node (ref "R4") (pin "2") (pinfunction "2_2") (pintype "passive"))
      (node (ref "R5") (pin "1") (pinfunction "1_1") (pintype "passive"))
      (node (ref "U4") (pin "5") (pinfunction "IN+_5") (pintype "input"))
    )
    (net (code "10") (name "/IN+_B_2") (class "Default")
      (node (ref "R7") (pin "2") (pinfunction "2_2") (pintype "passive"))
      (node (ref "R9") (pin "1") (pinfunction "1_1") (pintype "passive"))
      (node (ref "U7") (pin "5") (pinfunction "IN+_5") (pintype "input"))
    )
    (net (code "11") (name "/IN-_B") (class "Default")
      (node (ref "R3") (pin "2") (pinfunction "2_2") (pintype "passive"))
      (node (ref "R6") (pin "2") (pinfunction "2_2") (pintype "passive"))
      (node (ref "U4") (pin "6") (pinfunction "IN-_6") (pintype "input"))
    )
    (net (code "12") (name "/IN-_B_2") (class "Default")
      (node (ref "R11") (pin "2") (pinfunction "2_2") (pintype "passive"))
      (node (ref "R12") (pin "2") (pinfunction "2_2") (pintype "passive"))
      (node (ref "U7") (pin "6") (pinfunction "IN-_6") (pintype "input"))
    )
    (net (code "13") (name "/ISO_3V3_CLEAN") (class "Default")
      (node (ref "C10") (pin "2") (pinfunction "2_2") (pintype "passive"))
      (node (ref "C21") (pin "2") (pinfunction "2_2") (pintype "passive"))
      (node (ref "C9") (pin "2") (pinfunction "2_2") (pintype "passive"))
      (node (ref "J3") (pin "2") (pinfunction "2_2") (pintype "passive"))
      (node (ref "R1") (pin "1") (pinfunction "1_1") (pintype "passive"))
      (node (ref "TP9") (pin "TP") (pinfunction "TP_TP") (pintype "passive"))
      (node (ref "U2") (pin "5") (pinfunction "OUT_5") (pintype "power_in"))
      (node (ref "U3") (pin "4") (pinfunction "AVDD_VREF_4") (pintype "power_in"))
    )
    (net (code "14") (name "/ISO_3V3_CLEAN_2") (class "Default")
      (node (ref "C22") (pin "2") (pinfunction "2_2") (pintype "passive"))
      (node (ref "C23") (pin "2") (pinfunction "2_2") (pintype "passive"))
      (node (ref "C38") (pin "2") (pinfunction "2_2") (pintype "passive"))
      (node (ref "J4") (pin "2") (pinfunction "2_2") (pintype "passive"))
      (node (ref "R10") (pin "1") (pinfunction "1_1") (pintype "passive"))
      (node (ref "TP11") (pin "TP") (pinfunction "TP_TP") (pintype "passive"))
      (node (ref "U5") (pin "4") (pinfunction "AVDD_VREF_4") (pintype "power_in"))
      (node (ref "U8") (pin "5") (pinfunction "OUT_5") (pintype "power_in"))
    )
    (net (code "15") (name "/ISO_3V3_RAW") (class "Default")
      (node (ref "C5") (pin "1") (pinfunction "1_1") (pintype "passive"))
      (node (ref "C6") (pin "2") (pinfunction "2_2") (pintype "passive"))
      (node (ref "C8") (pin "2") (pinfunction "2_2") (pintype "passive"))
      (node (ref "TP10") (pin "TP") (pinfunction "TP_TP") (pintype "passive"))
      (node (ref "U1") (pin "12") (pinfunction "VISOOUT_12") (pintype "power_in"))
      (node (ref "U1") (pin "14") (pinfunction "EN_IO2_14") (pintype "input"))
      (node (ref "U1") (pin "20") (pinfunction "VISOIN_20") (pintype "power_in"))
      (node (ref "U2") (pin "1") (pinfunction "IN_1") (pintype "power_in"))
      (node (ref "U2") (pin "3") (pinfunction "EN_3") (pintype "input"))
    )
    (net (code "16") (name "/ISO_3V3_RAW_2") (class "Default")
      (node (ref "C25") (pin "1") (pinfunction "1_1") (pintype "passive"))
      (node (ref "C26") (pin "2") (pinfunction "2_2") (pintype "passive"))
      (node (ref "C36") (pin "2") (pinfunction "2_2") (pintype "passive"))
      (node (ref "TP12") (pin "TP") (pinfunction "TP_TP") (pintype "passive"))
      (node (ref "U6") (pin "12") (pinfunction "VISOOUT_12") (pintype "power_in"))
      (node (ref "U6") (pin "14") (pinfunction "EN_IO2_14") (pintype "input"))
      (node (ref "U6") (pin "20") (pinfunction "VISOIN_20") (pintype "power_in"))
      (node (ref "U8") (pin "1") (pinfunction "IN_1") (pintype "power_in"))
      (node (ref "U8") (pin "3") (pinfunction "EN_3") (pintype "input"))
    )
    (net (code "17") (name "/ISO_GND_ISOW") (class "Default")
      (node (ref "C10") (pin "1") (pinfunction "1_1") (pintype "passive"))
      (node (ref "C12") (pin "1") (pinfunction "1_1") (pintype "passive"))
      (node (ref "C13") (pin "1") (pinfunction "1_1") (pintype "passive"))
      (node (ref "C14") (pin "1") (pinfunction "1_1") (pintype "passive"))
      (node (ref "C15") (pin "1") (pinfunction "1_1") (pintype "passive"))
      (node (ref "C16") (pin "2") (pinfunction "2_2") (pintype "passive"))
      (node (ref "C17") (pin "2") (pinfunction "2_2") (pintype "passive"))
      (node (ref "C18") (pin "1") (pinfunction "1_1") (pintype "passive"))
      (node (ref "C19") (pin "2") (pinfunction "2_2") (pintype "passive"))
      (node (ref "C20") (pin "1") (pinfunction "1_1") (pintype "passive"))
      (node (ref "C21") (pin "1") (pinfunction "1_1") (pintype "passive"))
      (node (ref "C5") (pin "2") (pinfunction "2_2") (pintype "passive"))
      (node (ref "C6") (pin "1") (pinfunction "1_1") (pintype "passive"))
      (node (ref "C8") (pin "1") (pinfunction "1_1") (pintype "passive"))
      (node (ref "C9") (pin "1") (pinfunction "1_1") (pintype "passive"))
      (node (ref "J3") (pin "3") (pinfunction "3_3") (pintype "passive"))
      (node (ref "PS1") (pin "5") (pinfunction "0_5") (pintype "output"))
      (node (ref "R2") (pin "2") (pinfunction "2_2") (pintype "passive"))
      (node (ref "R5") (pin "2") (pinfunction "2_2") (pintype "passive"))
      (node (ref "TP3") (pin "TP") (pinfunction "TP_TP") (pintype "passive"))
      (node (ref "U1") (pin "11") (pinfunction "GND2_11") (pintype "power_in"))
      (node (ref "U1") (pin "13") (pinfunction "VSEL_13") (pintype "input"))
      (node (ref "U1") (pin "15") (pinfunction "GND2_15") (pintype "power_in"))
      (node (ref "U2") (pin "2") (pinfunction "GND_2") (pintype "power_in"))
      (node (ref "U3") (pin "5") (pinfunction "GND_5") (pintype "power_in"))
    )
    (net (code "18") (name "/ISO_GND_ISOW_2") (class "Default")
      (node (ref "C22") (pin "1") (pinfunction "1_1") (pintype "passive"))
      (node (ref "C23") (pin "1") (pinfunction "1_1") (pintype "passive"))
      (node (ref "C25") (pin "2") (pinfunction "2_2") (pintype "passive"))
      (node (ref "C26") (pin "1") (pinfunction "1_1") (pintype "passive"))
      (node (ref "C28") (pin "1") (pinfunction "1_1") (pintype "passive"))
      (node (ref "C29") (pin "1") (pinfunction "1_1") (pintype "passive"))
      (node (ref "C30") (pin "1") (pinfunction "1_1") (pintype "passive"))
      (node (ref "C31") (pin "1") (pinfunction "1_1") (pintype "passive"))
      (node (ref "C32") (pin "2") (pinfunction "2_2") (pintype "passive"))
      (node (ref "C33") (pin "1") (pinfunction "1_1") (pintype "passive"))
      (node (ref "C34") (pin "2") (pinfunction "2_2") (pintype "passive"))
      (node (ref "C35") (pin "2") (pinfunction "2_2") (pintype "passive"))
      (node (ref "C36") (pin "1") (pinfunction "1_1") (pintype "passive"))
      (node (ref "C37") (pin "1") (pinfunction "1_1") (pintype "passive"))
      (node (ref "C38") (pin "1") (pinfunction "1_1") (pintype "passive"))
      (node (ref "J4") (pin "3") (pinfunction "3_3") (pintype "passive"))
      (node (ref "PS2") (pin "5") (pinfunction "0_5") (pintype "output"))
      (node (ref "R8") (pin "2") (pinfunction "2_2") (pintype "passive"))
      (node (ref "R9") (pin "2") (pinfunction "2_2") (pintype "passive"))
      (node (ref "TP15") (pin "TP") (pinfunction "TP_TP") (pintype "passive"))
      (node (ref "U5") (pin "5") (pinfunction "GND_5") (pintype "power_in"))
      (node (ref "U6") (pin "11") (pinfunction "GND2_11") (pintype "power_in"))
      (node (ref "U6") (pin "13") (pinfunction "VSEL_13") (pintype "input"))
      (node (ref "U6") (pin "15") (pinfunction "GND2_15") (pintype "power_in"))
      (node (ref "U8") (pin "2") (pinfunction "GND_2") (pintype "power_in"))
    )
    (net (code "19") (name "/ISO_N5V") (class "Default")
      (node (ref "C13") (pin "2") (pinfunction "2_2") (pintype "passive"))
      (node (ref "C14") (pin "2") (pinfunction "2_2") (pintype "passive"))
      (node (ref "C18") (pin "2") (pinfunction "2_2") (pintype "passive"))
      (node (ref "C20") (pin "2") (pinfunction "2_2") (pintype "passive"))
      (node (ref "PS1") (pin "4") (pinfunction "-VOUT_4") (pintype "output"))
      (node (ref "TP2") (pin "TP") (pinfunction "TP_TP") (pintype "passive"))
      (node (ref "U4") (pin "4") (pinfunction "V-_4") (pintype "power_in"))
    )
    (net (code "20") (name "/ISO_N5V_2") (class "Default")
      (node (ref "C28") (pin "2") (pinfunction "2_2") (pintype "passive"))
      (node (ref "C31") (pin "2") (pinfunction "2_2") (pintype "passive"))
      (node (ref "C33") (pin "2") (pinfunction "2_2") (pintype "passive"))
      (node (ref "C37") (pin "2") (pinfunction "2_2") (pintype "passive"))
      (node (ref "PS2") (pin "4") (pinfunction "-VOUT_4") (pintype "output"))
      (node (ref "TP14") (pin "TP") (pinfunction "TP_TP") (pintype "passive"))
      (node (ref "U7") (pin "4") (pinfunction "V-_4") (pintype "power_in"))
    )
    (net (code "21") (name "/ISO_P5V") (class "Default")
      (node (ref "C12") (pin "2") (pinfunction "2_2") (pintype "passive"))
      (node (ref "C15") (pin "2") (pinfunction "2_2") (pintype "passive"))
      (node (ref "C17") (pin "1") (pinfunction "1_1") (pintype "passive"))
      (node (ref "C19") (pin "1") (pinfunction "1_1") (pintype "passive"))
      (node (ref "PS1") (pin "6") (pinfunction "+VOUT_6") (pintype "output"))
      (node (ref "TP1") (pin "TP") (pinfunction "TP_TP") (pintype "passive"))
      (node (ref "U4") (pin "8") (pinfunction "V+_8") (pintype "power_in"))
    )
    (net (code "22") (name "/ISO_P5V_2") (class "Default")
      (node (ref "C29") (pin "2") (pinfunction "2_2") (pintype "passive"))
      (node (ref "C30") (pin "2") (pinfunction "2_2") (pintype "passive"))
      (node (ref "C34") (pin "1") (pinfunction "1_1") (pintype "passive"))
      (node (ref "C35") (pin "1") (pinfunction "1_1") (pintype "passive"))
      (node (ref "PS2") (pin "6") (pinfunction "+VOUT_6") (pintype "output"))
      (node (ref "TP13") (pin "TP") (pinfunction "TP_TP") (pintype "passive"))
      (node (ref "U7") (pin "8") (pinfunction "V+_8") (pintype "power_in"))
    )
    (net (code "23") (name "/MID_RAW") (class "Default")
      (node (ref "C16") (pin "1") (pinfunction "1_1") (pintype "passive"))
      (node (ref "R1") (pin "2") (pinfunction "2_2") (pintype "passive"))
      (node (ref "R2") (pin "1") (pinfunction "1_1") (pintype "passive"))
      (node (ref "U4") (pin "3") (pinfunction "IN+_3") (pintype "input"))
    )
    (net (code "24") (name "/MID_RAW_2") (class "Default")
      (node (ref "C32") (pin "1") (pinfunction "1_1") (pintype "passive"))
      (node (ref "R10") (pin "2") (pinfunction "2_2") (pintype "passive"))
      (node (ref "R8") (pin "1") (pinfunction "1_1") (pintype "passive"))
      (node (ref "U7") (pin "3") (pinfunction "IN+_3") (pintype "input"))
    )
    (net (code "25") (name "/MOSI_ISO") (class "Default")
      (node (ref "U1") (pin "18") (pinfunction "OUTB_18") (pintype "output"))
      (node (ref "U3") (pin "3") (pinfunction "DIN_3") (pintype "input"))
    )
    (net (code "26") (name "/MOSI_ISO_2") (class "Default")
      (node (ref "U5") (pin "3") (pinfunction "DIN_3") (pintype "input"))
      (node (ref "U6") (pin "18") (pinfunction "OUTB_18") (pintype "output"))
    )
    (net (code "27") (name "/SCLK_ISO") (class "Default")
      (node (ref "U1") (pin "19") (pinfunction "OUTA_19") (pintype "output"))
      (node (ref "U3") (pin "2") (pinfunction "SCLK_2") (pintype "input"))
    )
    (net (code "28") (name "/SCLK_ISO_2") (class "Default")
      (node (ref "U5") (pin "2") (pinfunction "SCLK_2") (pintype "input"))
      (node (ref "U6") (pin "19") (pinfunction "OUTA_19") (pintype "output"))
    )
    (net (code "29") (name "/SPI_CS_SYS") (class "Default")
      (node (ref "J1") (pin "06") (pinfunction "06_06") (pintype "passive"))
      (node (ref "U1") (pin "4") (pinfunction "INC_4") (pintype "input"))
    )
    (net (code "30") (name "/SPI_CS_SYS_2") (class "Default")
      (node (ref "J2") (pin "06") (pinfunction "06_06") (pintype "passive"))
      (node (ref "U6") (pin "4") (pinfunction "INC_4") (pintype "input"))
    )
    (net (code "31") (name "/SPI_MOSI_SYS") (class "Default")
      (node (ref "J1") (pin "05") (pinfunction "05_05") (pintype "passive"))
      (node (ref "J2") (pin "05") (pinfunction "05_05") (pintype "passive"))
      (node (ref "U1") (pin "3") (pinfunction "INB_3") (pintype "input"))
      (node (ref "U6") (pin "3") (pinfunction "INB_3") (pintype "input"))
    )
    (net (code "32") (name "/SPI_SCLK_SYS") (class "Default")
      (node (ref "J1") (pin "04") (pinfunction "04_04") (pintype "passive"))
      (node (ref "J2") (pin "04") (pinfunction "04_04") (pintype "passive"))
      (node (ref "U1") (pin "2") (pinfunction "INA_2") (pintype "input"))
      (node (ref "U6") (pin "2") (pinfunction "INA_2") (pintype "input"))
    )
    (net (code "33") (name "/SYS_3V3") (class "Default")
      (node (ref "C1") (pin "1") (pinfunction "1_1") (pintype "passive"))
      (node (ref "C2") (pin "1") (pinfunction "1_1") (pintype "passive"))
      (node (ref "C24") (pin "2") (pinfunction "2_2") (pintype "passive"))
      (node (ref "C27") (pin "2") (pinfunction "2_2") (pintype "passive"))
      (node (ref "C3") (pin "2") (pinfunction "2_2") (pintype "passive"))
      (node (ref "C39") (pin "1") (pinfunction "1_1") (pintype "passive"))
      (node (ref "C4") (pin "2") (pinfunction "2_2") (pintype "passive"))
      (node (ref "C40") (pin "1") (pinfunction "1_1") (pintype "passive"))
      (node (ref "J1") (pin "02") (pinfunction "02_02") (pintype "passive"))
      (node (ref "J2") (pin "02") (pinfunction "02_02") (pintype "passive"))
      (node (ref "PS1") (pin "1") (pinfunction "+VIN_1") (pintype "input"))
      (node (ref "PS2") (pin "1") (pinfunction "+VIN_1") (pintype "input"))
      (node (ref "TP8") (pin "TP") (pinfunction "TP_TP") (pintype "passive"))
      (node (ref "U1") (pin "1") (pinfunction "VIO_1") (pintype "power_in"))
      (node (ref "U1") (pin "7") (pinfunction "EN_IO1_7") (pintype "input"))
      (node (ref "U1") (pin "8") (pinfunction "EN_DCDC_8") (pintype "bidirectional"))
      (node (ref "U1") (pin "9") (pinfunction "VDD_9") (pintype "power_in"))
      (node (ref "U6") (pin "1") (pinfunction "VIO_1") (pintype "power_in"))
      (node (ref "U6") (pin "7") (pinfunction "EN_IO1_7") (pintype "input"))
      (node (ref "U6") (pin "8") (pinfunction "EN_DCDC_8") (pintype "bidirectional"))
      (node (ref "U6") (pin "9") (pinfunction "VDD_9") (pintype "power_in"))
    )
    (net (code "34") (name "/SYS_GND") (class "Default")
      (node (ref "C1") (pin "2") (pinfunction "2_2") (pintype "passive"))
      (node (ref "C2") (pin "2") (pinfunction "2_2") (pintype "passive"))
      (node (ref "C24") (pin "1") (pinfunction "1_1") (pintype "passive"))
      (node (ref "C27") (pin "1") (pinfunction "1_1") (pintype "passive"))
      (node (ref "C3") (pin "1") (pinfunction "1_1") (pintype "passive"))
      (node (ref "C39") (pin "2") (pinfunction "2_2") (pintype "passive"))
      (node (ref "C4") (pin "1") (pinfunction "1_1") (pintype "passive"))
      (node (ref "C40") (pin "2") (pinfunction "2_2") (pintype "passive"))
      (node (ref "J1") (pin "03") (pinfunction "03_03") (pintype "passive"))
      (node (ref "J2") (pin "03") (pinfunction "03_03") (pintype "passive"))
      (node (ref "PS1") (pin "2") (pinfunction "-VIN_2") (pintype "input"))
      (node (ref "PS2") (pin "2") (pinfunction "-VIN_2") (pintype "input"))
      (node (ref "U1") (pin "10") (pinfunction "GND1_10") (pintype "power_in"))
      (node (ref "U1") (pin "6") (pinfunction "GND1_6") (pintype "power_in"))
      (node (ref "U6") (pin "10") (pinfunction "GND1_10") (pintype "power_in"))
      (node (ref "U6") (pin "6") (pinfunction "GND1_6") (pintype "power_in"))
    )
    (net (code "35") (name "/VBUS_5V") (class "Default")
      (node (ref "J1") (pin "01") (pinfunction "01_01") (pintype "passive+no_connect"))
    )
    (net (code "36") (name "/VBUS_5V_2") (class "Default")
      (node (ref "J2") (pin "01") (pinfunction "01_01") (pintype "passive+no_connect"))
    )
    (net (code "37") (name "/VREF_MID") (class "Default")
      (node (ref "R4") (pin "1") (pinfunction "1_1") (pintype "passive"))
      (node (ref "TP7") (pin "TP") (pinfunction "TP_TP") (pintype "passive"))
      (node (ref "U4") (pin "1") (pinfunction "OUT_1") (pintype "output"))
      (node (ref "U4") (pin "2") (pinfunction "IN-_2") (pintype "input"))
    )
    (net (code "38") (name "/VREF_MID_2") (class "Default")
      (node (ref "R7") (pin "1") (pinfunction "1_1") (pintype "passive"))
      (node (ref "TP17") (pin "TP") (pinfunction "TP_TP") (pintype "passive"))
      (node (ref "U7") (pin "1") (pinfunction "OUT_1") (pintype "output"))
      (node (ref "U7") (pin "2") (pinfunction "IN-_2") (pintype "input"))
    )
    (net (code "39") (name "unconnected-(U1-IND-Pad16)") (class "Default")
      (node (ref "U1") (pin "16") (pinfunction "IND_16") (pintype "input+no_connect"))
    )
    (net (code "40") (name "unconnected-(U1-OUTD-Pad5)") (class "Default")
      (node (ref "U1") (pin "5") (pinfunction "OUTD_5") (pintype "output"))
    )
    (net (code "41") (name "unconnected-(U2-NC-Pad4)") (class "Default")
      (node (ref "U2") (pin "4") (pinfunction "NC_4") (pintype "passive"))
    )
    (net (code "42") (name "unconnected-(U6-IND-Pad16)") (class "Default")
      (node (ref "U6") (pin "16") (pinfunction "IND_16") (pintype "input+no_connect"))
    )
    (net (code "43") (name "unconnected-(U6-OUTD-Pad5)") (class "Default")
      (node (ref "U6") (pin "5") (pinfunction "OUTD_5") (pintype "output"))
    )
    (net (code "44") (name "unconnected-(U8-NC-Pad4)") (class "Default")
      (node (ref "U8") (pin "4") (pinfunction "NC_4") (pintype "passive"))
    )
  )
)
